# WX0_007_101DL.net
KiCad netlist of a schematic drawn in Altium Designer
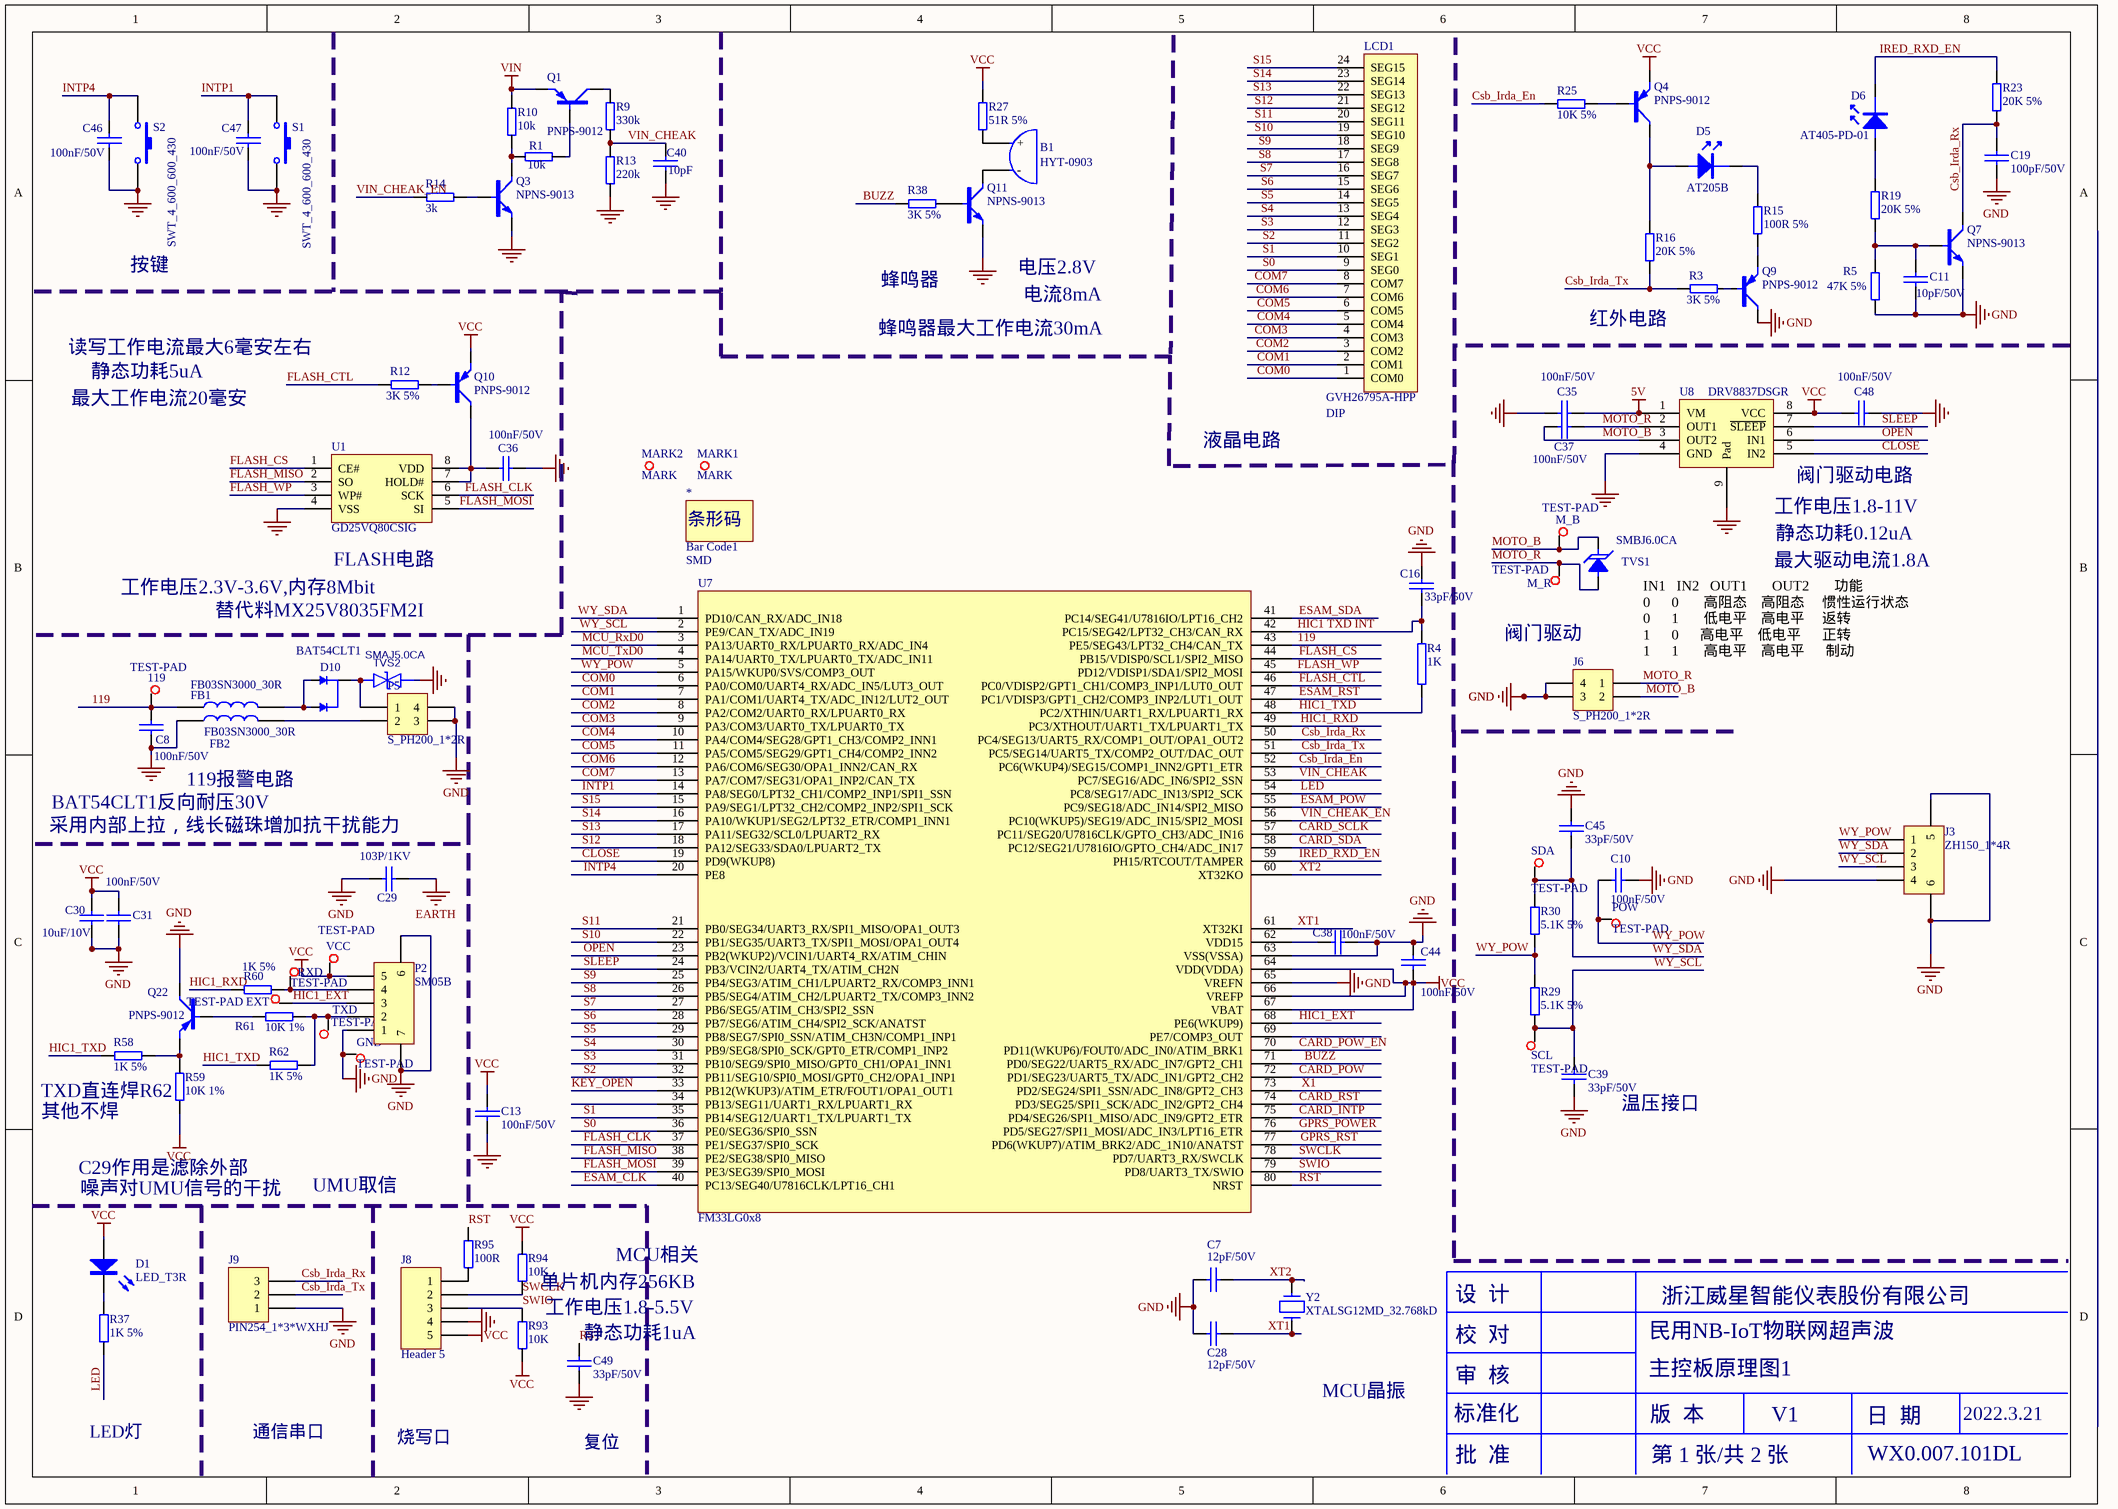
[diagram p0: WX0.007.101DL.SchDoc]

(export (version "E")
  (design (tool "Eeschema 10.0.6"))
  (components
    (comp (ref "*")
      (value "Bar Code1")
      (footprint "Bar Code1")
      (description "条形码 ,填充，无需焊接器件")
      (fields (field (name "PART NUMBER") "AD_WXHJ_Bar Code_02") (field (name "SMD/DIP") "SMD"))
      (libsource (lib "Database_Libs2") (part "05_AD_WXHJ_Bar Code_02"))
    )
    (comp (ref "119")
      (value "TEST-PAD")
      (footprint "TEST-PAD")
      (description "单面焊盘测试点")
      (fields (field (name "PART NUMBER") "AD_WXHJ_TEST-PAD_01"))
      (libsource (lib "Database_Libs2") (part "TEST-PAD"))
    )
    (comp (ref "B1")
      (value "HYT-0903")
      (footprint "HYT-0903")
      (description "直插,直径9mm,高5.5mm,5 V,2 V,30 mA,兴化市华宇电子有限公司,HYT-0903")
      (fields (field (name "PART NUMBER") "1010602-0007"))
      (libsource (lib "Database_Libs2") (part "07_HYT-0903"))
    )
    (comp (ref "C7")
      (value "12pF/50V")
      (footprint "CAP0603")
      (description "12P,50 V,±5%,0603,国巨,CC0603JRNPO9BN12")
      (fields (field (name "PART NUMBER") "101020103-0005"))
      (libsource (lib "Database_Libs2") (part "CC03JPO9_12P"))
    )
    (comp (ref "C8")
      (value "100nF/50V")
      (footprint "CAP0603")
      (description "104pF,50 V,±10%,0603,国巨,CC0603KRX7R9BB104")
      (fields (field (name "PART NUMBER") "101020103-0021"))
      (libsource (lib "Database_Libs2") (part "CC03K7R9_100N"))
    )
    (comp (ref "C10")
      (value "100nF/50V")
      (footprint "CAP0603")
      (description "104pF,50 V,±10%,0603,国巨,CC0603KRX7R9BB104")
      (fields (field (name "PART NUMBER") "101020103-0021"))
      (libsource (lib "Database_Libs2") (part "CC03K7R9_100N"))
    )
    (comp (ref "C11")
      (value "10pF/50V")
      (footprint "CAP0603")
      (description "10pF,50 V,±5%,0603,X7R,国巨,CC0603JRNPO9BN100")
      (fields (field (name "PART NUMBER") "101020103-0014"))
      (libsource (lib "Database_Libs2") (part "CC03JPO9_10P"))
    )
    (comp (ref "C13")
      (value "100nF/50V")
      (footprint "CAP0603")
      (description "104pF,50 V,±10%,0603,国巨,CC0603KRX7R9BB104")
      (fields (field (name "PART NUMBER") "101020103-0021"))
      (libsource (lib "Database_Libs2") (part "CC03K7R9_100N"))
    )
    (comp (ref "C16")
      (value "33pF/50V")
      (footprint "CAP0603")
      (description "33pF,50 V,±10%,0603,国巨,CC0603KRNPO9BN33")
      (fields (field (name "PART NUMBER") "101020103-0027"))
      (libsource (lib "Database_Libs2") (part "CC03KPO9_33P"))
    )
    (comp (ref "C19")
      (value "100pF/50V")
      (footprint "CAP0603")
      (description "101pf,50 V,±5%,0603,国巨,CC0603JRNP09BN101")
      (fields (field (name "PART NUMBER") "101020103-0010"))
      (libsource (lib "Database_Libs2") (part "CC03JPO9_101P"))
    )
    (comp (ref "C28")
      (value "12pF/50V")
      (footprint "CAP0603")
      (description "12P,50 V,±5%,0603,国巨,CC0603JRNPO9BN12")
      (fields (field (name "PART NUMBER") "101020103-0005"))
      (libsource (lib "Database_Libs2") (part "CC03JPO9_12P"))
    )
    (comp (ref "C29")
      (value "103P/1KV")
      (footprint "CAP1206")
      (description "103P/1KV,±10％,1206")
      (fields (field (name "PART NUMBER") "101020101-0003"))
      (libsource (lib "altium-import") (part "root_3_CC03K7R9_100N_"))
    )
    (comp (ref "C30")
      (value "10uF/10V")
      (footprint "CAP0603")
      (description "106pF,10 V,±10%,0603,村田,GRM188R61A106KE47D")
      (fields (field (name "PART NUMBER") "101020103-0026"))
      (libsource (lib "Database_Libs2") (part "CC03K5R6_10U"))
    )
    (comp (ref "C31")
      (value "100nF/50V")
      (footprint "CAP0603")
      (description "104pF,50 V,±10%,0603,国巨,CC0603KRX7R9BB104")
      (fields (field (name "PART NUMBER") "101020103-0021"))
      (libsource (lib "Database_Libs2") (part "CC03K7R9_100N"))
    )
    (comp (ref "C35")
      (value "100nF/50V")
      (footprint "CAP0603")
      (description "104pF,50 V,±10%,0603,国巨,CC0603KRX7R9BB104")
      (fields (field (name "PART NUMBER") "101020103-0021"))
      (libsource (lib "Database_Libs2") (part "CC03K7R9_100N"))
    )
    (comp (ref "C36")
      (value "100nF/50V")
      (footprint "CAP0603")
      (description "104pF,50 V,±10%,0603,国巨,CC0603KRX7R9BB104")
      (fields (field (name "PART NUMBER") "101020103-0021"))
      (libsource (lib "Database_Libs2") (part "CC03K7R9_100N"))
    )
    (comp (ref "C37")
      (value "100nF/50V")
      (footprint "CAP0603")
      (description "104pF,50 V,±10%,0603,国巨,CC0603KRX7R9BB104")
      (fields (field (name "PART NUMBER") "101020103-0021"))
      (libsource (lib "Database_Libs2") (part "CC03K7R9_100N"))
    )
    (comp (ref "C38")
      (value "100nF/50V")
      (footprint "CAP0603")
      (description "104pF,50 V,±10%,0603,国巨,CC0603KRX7R9BB104")
      (fields (field (name "PART NUMBER") "101020103-0021"))
      (libsource (lib "Database_Libs2") (part "CC03K7R9_100N"))
    )
    (comp (ref "C39")
      (value "33pF/50V")
      (footprint "CAP0603")
      (description "33pF,50 V,±10%,0603,国巨,CC0603KRNPO9BN33")
      (fields (field (name "PART NUMBER") "101020103-0027"))
      (libsource (lib "Database_Libs2") (part "CC03KPO9_33P"))
    )
    (comp (ref "C40")
      (value "10pF")
      (footprint "CAP0603")
      (description "无极性电容")
      (libsource (lib "CBB_Lib_SCH") (part "CAP"))
    )
    (comp (ref "C44")
      (value "100nF/50V")
      (footprint "CAP0603")
      (description "104pF,50 V,±10%,0603,国巨,CC0603KRX7R9BB104")
      (fields (field (name "PART NUMBER") "101020103-0021"))
      (libsource (lib "Database_Libs2") (part "CC03K7R9_100N"))
    )
    (comp (ref "C45")
      (value "33pF/50V")
      (footprint "CAP0603")
      (description "33pF,50 V,±10%,0603,国巨,CC0603KRNPO9BN33")
      (fields (field (name "PART NUMBER") "101020103-0027"))
      (libsource (lib "Database_Libs2") (part "CC03KPO9_33P"))
    )
    (comp (ref "C46")
      (value "100nF/50V")
      (footprint "CAP0603")
      (description "104pF,50 V,±10%,0603,国巨,CC0603KRX7R9BB104")
      (fields (field (name "PART NUMBER") "101020103-0021"))
      (libsource (lib "Database_Libs2") (part "CC03K7R9_100N"))
    )
    (comp (ref "C47")
      (value "100nF/50V")
      (footprint "CAP0603")
      (description "104pF,50 V,±10%,0603,国巨,CC0603KRX7R9BB104")
      (fields (field (name "PART NUMBER") "101020103-0021"))
      (libsource (lib "Database_Libs2") (part "CC03K7R9_100N"))
    )
    (comp (ref "C48")
      (value "100nF/50V")
      (footprint "CAP0603")
      (description "104pF,50 V,±10%,0603,国巨,CC0603KRX7R9BB104")
      (fields (field (name "PART NUMBER") "101020103-0021"))
      (libsource (lib "Database_Libs2") (part "CC03K7R9_100N"))
    )
    (comp (ref "C49")
      (value "33pF/50V")
      (footprint "CAP0603")
      (description "33pF,50 V,±10%,0603,国巨,CC0603KRNPO9BN33")
      (fields (field (name "PART NUMBER") "101020103-0027"))
      (libsource (lib "Database_Libs2") (part "CC03KPO9_33P"))
    )
    (comp (ref "D1")
      (value "LED_T3R")
      (footprint "LED2_300")
      (description "圆形插件,3mm 圆形,插件,红光,湖北匡通电子有限公司,3BB4HC")
      (fields (field (name "PART NUMBER") "101040102-0001"))
      (libsource (lib "Database_Libs2") (part "01-LED_T3R"))
    )
    (comp (ref "D5")
      (value "AT205B")
      (footprint "IR_254_1000_500")
      (description "直插,Φ5.8mm圆头透明色，,0.1 A,4 V,5 V,上海品观电子有限公司,AT205B")
      (fields (field (name "PART NUMBER") "101040101-0034"))
      (libsource (lib "Database_Libs2") (part "01_AT205B"))
    )
    (comp (ref "D6")
      (value "AT405-PD-01")
      (footprint "IR_254_1000_500")
      (description "Φ5.8mm圆头黑色，光电接收管,Φ5.8mm,0.01 A,1.2 V,60 V,上海品观电子,AT405-PD-01")
      (fields (field (name "PART NUMBER") "101040101-0035"))
      (libsource (lib "Database_Libs2") (part "01_AT405-PD-01"))
    )
    (comp (ref "D10")
      (value "BAT54CLT1")
      (footprint "SOT-23")
      (description "BAT54CLT1，SOT23-3,SOT23-3,0.2 A,0.8 V,30 V,安森美,BAT54CLT1")
      (fields (field (name "PART NUMBER") "101040101-0038"))
      (libsource (lib "Database_Libs2") (part "02_BAT54CLT1"))
    )
    (comp (ref "EXT")
      (value "TEST-PAD")
      (footprint "TEST-PAD")
      (description "单面焊盘测试点")
      (fields (field (name "PART NUMBER") "AD_WXHJ_TEST-PAD_01"))
      (libsource (lib "Database_Libs2") (part "TEST-PAD"))
    )
    (comp (ref "FB1")
      (value "FB03SN3000_30R")
      (footprint "IND0603")
      (description "chilisin(奇力新),0603,30Ω ±25% @100MHz,150 V,125 ℃,PBY160808T-300Y-N,-55 ℃,不含铅,,,圆盘,30Ω ±25% @100MHz")
      (fields (field (name "PART NUMBER") "109010101-0003"))
      (libsource (lib "Database_Libs2") (part "06_FB03SN3000_30R"))
    )
    (comp (ref "FB2")
      (value "FB03SN3000_30R")
      (footprint "IND0603")
      (description "chilisin(奇力新),0603,30Ω ±25% @100MHz,150 V,125 ℃,PBY160808T-300Y-N,-55 ℃,不含铅,,,圆盘,30Ω ±25% @100MHz")
      (fields (field (name "PART NUMBER") "109010101-0003"))
      (libsource (lib "Database_Libs2") (part "06_FB03SN3000_30R"))
    )
    (comp (ref "GND")
      (value "TEST-PAD")
      (footprint "TEST-PAD")
      (description "单面焊盘测试点")
      (fields (field (name "PART NUMBER") "AD_WXHJ_TEST-PAD_01"))
      (libsource (lib "Database_Libs2") (part "TEST-PAD"))
    )
    (comp (ref "J3")
      (value "ZH150_1*4R")
      (footprint "SMT-1.5-4")
      (description "4针1.5mm间距，贴片卧式,9.0mm*6.5mm,公头,单排,4针1.5mm间距，贴片卧式")
      (fields (field (name "PART NUMBER") "1010902-0126"))
      (libsource (lib "Database_Libs2") (part "ZH150_1*4R"))
    )
    (comp (ref "J6")
      (value "S_PH200_1*2R")
      (footprint "SMT2-2.0")
      (description "PH2.0_2AWR 卧,贴片卧式,母头,单排,2针2.0mm")
      (fields (field (name "PART NUMBER") "1010902-0125"))
      (libsource (lib "") (part "S_PH200_1*2R_1"))
    )
    (comp (ref "J8")
      (value "Header 5")
      (footprint "PIN254_1*5SR")
      (description "Header, 5-Pin")
      (libsource (lib "CBB_Lib_SCH") (part "Header 5"))
    )
    (comp (ref "J9")
      (value "PIN254_1*3*WXHJ")
      (footprint "PIN254_1*3*WXHJ")
      (description "1*3 ，Φ1.0 ，2.54mm，直脚,无需焊接器件")
      (fields (field (name "PART NUMBER") "AD_WXHJ_PinHeader_04"))
      (libsource (lib "Database_Libs2") (part "PIN254_1*3*WXHJ"))
    )
    (comp (ref "LCD1")
      (value "GVH26795A-HPP")
      (footprint "JR-H25808ARP")
      (description "4.4V,61mm*23.5mm*26mm,针脚,段码,126,HTN,半透,60 ℃,-20 ℃,安徽金视界光电科技有限公司,GVH25995A-HPP")
      (fields (field (name "PART NUMBER") "1010801-0050") (field (name "SMD/DIP") "DIP"))
      (libsource (lib "Database_Libs2") (part "03_LCD_GVH25995A-HPP"))
    )
    (comp (ref "MARK1")
      (value "MARK")
      (footprint "MARK")
      (description "MARK点")
      (fields (field (name "PART NUMBER") "AD_WXHJ_MARK_01"))
      (libsource (lib "Database_Libs2") (part "MARK"))
    )
    (comp (ref "MARK2")
      (value "MARK")
      (footprint "MARK")
      (description "MARK点")
      (fields (field (name "PART NUMBER") "AD_WXHJ_MARK_01"))
      (libsource (lib "Database_Libs2") (part "MARK"))
    )
    (comp (ref "M_B")
      (value "TEST-PAD")
      (footprint "TEST-PAD")
      (description "单面焊盘测试点")
      (fields (field (name "PART NUMBER") "AD_WXHJ_TEST-PAD_01"))
      (libsource (lib "Database_Libs2") (part "TEST-PAD"))
    )
    (comp (ref "M_R")
      (value "TEST-PAD")
      (footprint "TEST-PAD")
      (description "单面焊盘测试点")
      (fields (field (name "PART NUMBER") "AD_WXHJ_TEST-PAD_01"))
      (libsource (lib "Database_Libs2") (part "TEST-PAD"))
    )
    (comp (ref "P2") (value "SM05B") (footprint "SMT-1.25-5") (libsource (lib "Connect_WX") (part "SM05B")))
    (comp (ref "P5")
      (value "S_PH200_1*2R")
      (footprint "SMT2-2.0")
      (description "PH2.0_2AWR 卧,贴片卧式,母头,单排,2针2.0mm")
      (fields (field (name "PART NUMBER") "1010902-0125"))
      (libsource (lib "Database_Libs2") (part "S_PH200_1*2R"))
    )
    (comp (ref "POW")
      (value "TEST-PAD")
      (footprint "TEST-PAD")
      (description "单面焊盘测试点")
      (fields (field (name "PART NUMBER") "AD_WXHJ_TEST-PAD_01"))
      (libsource (lib "Database_Libs2") (part "TEST-PAD"))
    )
    (comp (ref "Q1")
      (value "PNPS-9012")
      (footprint "SOT-23")
      (description "9012,PNP,SOT-23,JCET;长电,S9012")
      (fields (field (name "PART NUMBER") "101040201-0001"))
      (libsource (lib "Database_Libs2") (part "03_PNPS-9012"))
    )
    (comp (ref "Q3")
      (value "NPNS-9013")
      (footprint "SOT-23")
      (description "9013,NPN,SOT-23,长电,S9013")
      (fields (field (name "PART NUMBER") "101040201-0002"))
      (libsource (lib "Database_Libs2") (part "03_NPNS-9013"))
    )
    (comp (ref "Q4")
      (value "PNPS-9012")
      (footprint "SOT-23")
      (description "9012,PNP,SOT-23,JCET;长电,S9012")
      (fields (field (name "PART NUMBER") "101040201-0001"))
      (libsource (lib "Database_Libs2") (part "03_PNPS-9012"))
    )
    (comp (ref "Q7")
      (value "NPNS-9013")
      (footprint "SOT-23")
      (description "9013,NPN,SOT-23,长电,S9013")
      (fields (field (name "PART NUMBER") "101040201-0002"))
      (libsource (lib "Database_Libs2") (part "03_NPNS-9013"))
    )
    (comp (ref "Q9")
      (value "PNPS-9012")
      (footprint "SOT-23")
      (description "9012,PNP,SOT-23,JCET;长电,S9012")
      (fields (field (name "PART NUMBER") "101040201-0001"))
      (libsource (lib "Database_Libs2") (part "03_PNPS-9012"))
    )
    (comp (ref "Q10")
      (value "PNPS-9012")
      (footprint "SOT-23")
      (description "9012,PNP,SOT-23,JCET;长电,S9012")
      (fields (field (name "PART NUMBER") "101040201-0001"))
      (libsource (lib "Database_Libs2") (part "03_PNPS-9012"))
    )
    (comp (ref "Q11")
      (value "NPNS-9013")
      (footprint "SOT-23")
      (description "9013,NPN,SOT-23,长电,S9013")
      (fields (field (name "PART NUMBER") "101040201-0002"))
      (libsource (lib "Database_Libs2") (part "03_NPNS-9013"))
    )
    (comp (ref "Q22")
      (value "PNPS-9012")
      (footprint "SOT-23")
      (description "9012,PNP,SOT-23,JCET;长电,S9012")
      (fields (field (name "PART NUMBER") "101040201-0001"))
      (libsource (lib "Database_Libs2") (part "03_PNPS-9012"))
    )
    (comp (ref "R1") (value "10k") (footprint "RES0603") (libsource (lib "CBB_Lib_SCH") (part "RES")))
    (comp (ref "R3")
      (value "3K 5%")
      (footprint "RES0603")
      (description "国巨,±5%,0603,,155 ℃,-55 ℃,RC0603JR-073KL,无铅,100 ppm/℃,1/10W,,3K")
      (fields (field (name "PART NUMBER") "101010103-0006"))
      (libsource (lib "Database_Libs2") (part "RC03J_3K"))
    )
    (comp (ref "R4") (value "1K") (footprint "RES0603") (libsource (lib "PCB_Project1_1") (part "RES2")))
    (comp (ref "R5")
      (value "47K 5%")
      (footprint "RES0603")
      (description "47K,±5%,1/10W,0603,国巨,RC0603JR-0747KL")
      (fields (field (name "PART NUMBER") "101010103-0012"))
      (libsource (lib "Database_Libs2") (part "RC03J_47K"))
    )
    (comp (ref "R9") (value "330k") (footprint "RES0603") (libsource (lib "CBB_Lib_SCH") (part "RES")))
    (comp (ref "R10") (value "10k") (footprint "RES0603") (libsource (lib "CBB_Lib_SCH") (part "RES")))
    (comp (ref "R12")
      (value "3K 5%")
      (footprint "RES0603")
      (description "国巨,±5%,0603,,155 ℃,-55 ℃,RC0603JR-073KL,无铅,100 ppm/℃,1/10W,,3K")
      (fields (field (name "PART NUMBER") "101010103-0006"))
      (libsource (lib "Database_Libs2") (part "RC03J_3K"))
    )
    (comp (ref "R13") (value "220k") (footprint "RES0603") (libsource (lib "CBB_Lib_SCH") (part "RES")))
    (comp (ref "R14") (value "3k") (footprint "RES0603") (libsource (lib "CBB_Lib_SCH") (part "RES")))
    (comp (ref "R15")
      (value "100R 5%")
      (footprint "RES0603")
      (description "100R,±5%,1/10W,0603,国巨,RC0603JR-07100RL")
      (fields (field (name "PART NUMBER") "101010103-0022"))
      (libsource (lib "Database_Libs2") (part "RC03J_100R"))
    )
    (comp (ref "R16")
      (value "20K 5%")
      (footprint "RES0603")
      (description "国巨,±5%,0603,,155 ℃,-55 ℃,RC0603JR-0720KL,无铅,200 ppm/℃,1/10W,,20K")
      (fields (field (name "PART NUMBER") "101010103-0004"))
      (libsource (lib "Database_Libs2") (part "RC03J_20K"))
    )
    (comp (ref "R19")
      (value "20K 5%")
      (footprint "RES0603")
      (description "国巨,±5%,0603,,155 ℃,-55 ℃,RC0603JR-0720KL,无铅,200 ppm/℃,1/10W,,20K")
      (fields (field (name "PART NUMBER") "101010103-0004"))
      (libsource (lib "Database_Libs2") (part "RC03J_20K"))
    )
    (comp (ref "R23")
      (value "20K 5%")
      (footprint "RES0603")
      (description "国巨,±5%,0603,,155 ℃,-55 ℃,RC0603JR-0720KL,无铅,200 ppm/℃,1/10W,,20K")
      (fields (field (name "PART NUMBER") "101010103-0004"))
      (libsource (lib "Database_Libs2") (part "RC03J_20K"))
    )
    (comp (ref "R25")
      (value "10K 5%")
      (footprint "RES0603")
      (description "国巨,±5%,0603,,155 ℃,-55 ℃,RC0603JR-0710KL,无铅,200 ppm/℃,1/10W,,10K")
      (fields (field (name "PART NUMBER") "101010103-0003"))
      (libsource (lib "Database_Libs2") (part "RC03J_10K"))
    )
    (comp (ref "R27")
      (value "51R 5%")
      (footprint "RES0603")
      (description "国巨,±5%,0603,,155 ℃,-55 ℃,RC0603JR-0751RL,无铅,100 ppm/℃,1/10W,,51欧")
      (fields (field (name "PART NUMBER") "101010103-0037"))
      (libsource (lib "Database_Libs2") (part "RC03J_51R"))
    )
    (comp (ref "R29")
      (value "5.1K 5%")
      (footprint "RES0603")
      (description "国巨,±5%,0603,,155 ℃,55 ℃,RC0603JR-075.1KL,无铅,200 ppm/℃,1/10W,,5.1k")
      (fields (field (name "PART NUMBER") "101010103-0015"))
      (libsource (lib "Database_Libs2") (part "RC03J_5.1K"))
    )
    (comp (ref "R30")
      (value "5.1K 5%")
      (footprint "RES0603")
      (description "国巨,±5%,0603,,155 ℃,55 ℃,RC0603JR-075.1KL,无铅,200 ppm/℃,1/10W,,5.1k")
      (fields (field (name "PART NUMBER") "101010103-0015"))
      (libsource (lib "Database_Libs2") (part "RC03J_5.1K"))
    )
    (comp (ref "R37")
      (value "1K 5%")
      (footprint "RES0603")
      (description "1K,±5%,1/10W,0603,国巨,RC0603JR-071KL")
      (fields (field (name "PART NUMBER") "101010103-0008"))
      (libsource (lib "Database_Libs2") (part "RC03J_1K"))
    )
    (comp (ref "R38")
      (value "3K 5%")
      (footprint "RES0603")
      (description "国巨,±5%,0603,,155 ℃,-55 ℃,RC0603JR-073KL,无铅,100 ppm/℃,1/10W,,3K")
      (fields (field (name "PART NUMBER") "101010103-0006"))
      (libsource (lib "Database_Libs2") (part "RC03J_3K"))
    )
    (comp (ref "R58")
      (value "1K 5%")
      (footprint "RES0603")
      (description "1K,±5%,1/10W,0603,国巨,RC0603JR-071KL")
      (fields (field (name "PART NUMBER") "101010103-0008"))
      (libsource (lib "Database_Libs2") (part "RC03J_1K"))
    )
    (comp (ref "R59")
      (value "10K 1%")
      (footprint "RES0603")
      (description "10K±1%,1/10W,0603")
      (fields (field (name "PART NUMBER") "101010103-0052"))
      (libsource (lib "Database_Libs2") (part "RC03J_10K"))
    )
    (comp (ref "R60")
      (value "1K 5%")
      (footprint "RES0603")
      (description "1K,±5%,1/10W,0603,国巨,RC0603JR-071KL")
      (fields (field (name "PART NUMBER") "101010103-0008"))
      (libsource (lib "Database_Libs2") (part "RC03J_1K"))
    )
    (comp (ref "R61")
      (value "10K 1%")
      (footprint "RES0603")
      (description "10K±1%,1/10W,0603")
      (fields (field (name "PART NUMBER") "101010103-0052"))
      (libsource (lib "Database_Libs2") (part "RC03J_10K"))
    )
    (comp (ref "R62")
      (value "1K 5%")
      (footprint "RES0603")
      (description "1K,±5%,1/10W,0603,国巨,RC0603JR-071KL")
      (fields (field (name "PART NUMBER") "101010103-0008"))
      (libsource (lib "Database_Libs2") (part "RC03J_1K"))
    )
    (comp (ref "R93") (value "10K") (footprint "RES0603") (libsource (lib "CBB_Lib_SCH") (part "RES")))
    (comp (ref "R94") (value "10K") (footprint "RES0603") (libsource (lib "CBB_Lib_SCH") (part "RES")))
    (comp (ref "R95") (value "100R") (footprint "RES0603") (libsource (lib "CBB_Lib_SCH") (part "RES")))
    (comp (ref "RXD")
      (value "TEST-PAD")
      (footprint "TEST-PAD")
      (description "单面焊盘测试点")
      (fields (field (name "PART NUMBER") "AD_WXHJ_TEST-PAD_01"))
      (libsource (lib "Database_Libs2") (part "TEST-PAD"))
    )
    (comp (ref "S1")
      (value "SWT_4_600_600_430")
      (footprint "SWT_4_600_600")
      (description "TS-1102,机械轻触,6*6*4.3直插,6*6*4.3直插,乐清市羽欧电子")
      (fields (field (name "PART NUMBER") "1011001-0027"))
      (libsource (lib "Database_Libs2") (part "07_SWT_4_600_600_430"))
    )
    (comp (ref "S2")
      (value "SWT_4_600_600_430")
      (footprint "SWT_4_600_600")
      (description "TS-1102,机械轻触,6*6*4.3直插,6*6*4.3直插,乐清市羽欧电子")
      (fields (field (name "PART NUMBER") "1011001-0027"))
      (libsource (lib "Database_Libs2") (part "07_SWT_4_600_600_430"))
    )
    (comp (ref "SCL")
      (value "TEST-PAD")
      (footprint "TEST-PAD")
      (description "单面焊盘测试点")
      (fields (field (name "PART NUMBER") "AD_WXHJ_TEST-PAD_01"))
      (libsource (lib "Database_Libs2") (part "TEST-PAD"))
    )
    (comp (ref "SDA")
      (value "TEST-PAD")
      (footprint "TEST-PAD")
      (description "单面焊盘测试点")
      (fields (field (name "PART NUMBER") "AD_WXHJ_TEST-PAD_01"))
      (libsource (lib "Database_Libs2") (part "TEST-PAD"))
    )
    (comp (ref "TVS1")
      (value "SMBJ6.0CA")
      (footprint "DO-214AA")
      (description "SMBJ6.0CA,DO-214AA,10.3 V,6.0 V,600 W,58.3 A,800 uA,上海君耀电子有限公司,SMBJ6.0CA")
      (fields (field (name "PART NUMBER") "101040101-0024"))
      (libsource (lib "Database_Libs2") (part "05_SMBJ6.0CA"))
    )
    (comp (ref "TVS2")
      (value "SMAJ5.0CA")
      (footprint "SMAJ5.0CA")
      (fields (field (name "BOM_SUPPLIER PART") "C693487") (field (name "CONTRIBUTOR") "LCSC"))
      (libsource (lib "Discrete_WX") (part "SMAJ5.0CA_C693487"))
    )
    (comp (ref "TXD")
      (value "TEST-PAD")
      (footprint "TEST-PAD")
      (description "单面焊盘测试点")
      (fields (field (name "PART NUMBER") "AD_WXHJ_TEST-PAD_01"))
      (libsource (lib "Database_Libs2") (part "TEST-PAD"))
    )
    (comp (ref "U1")
      (value "GD25VQ80CSIG")
      (footprint "SOP-8L-200MIL")
      (description "GD25VQ80CSIG,SOP8 208mil,北京兆易创新科技股份有限公司,GD25VQ80CSIG")
      (fields (field (name "PART NUMBER") "101050101-0165"))
      (libsource (lib "Database_Libs2") (part "04_GD25VQ80CSIG"))
    )
    (comp (ref "U7") (value "FM33LG0x8") (footprint "LQFP80") (libsource (lib "FM_MCU") (part "FM33LG0x8")))
    (comp (ref "U8")
      (value "DRV8837DSGR")
      (footprint "S-PWSON-N8")
      (description "DRV8837DSGR,S-PWSON-N8,TI,DRV8837DSGR")
      (fields (field (name "PART NUMBER") "101050101-0060"))
      (libsource (lib "Database_Libs2") (part "07_DRV8837DSGR"))
    )
    (comp (ref "VCC")
      (value "TEST-PAD")
      (footprint "TEST-PAD")
      (description "单面焊盘测试点")
      (fields (field (name "PART NUMBER") "AD_WXHJ_TEST-PAD_01"))
      (libsource (lib "Database_Libs2") (part "TEST-PAD"))
    )
    (comp (ref "Y2")
      (value "XTALSG12MD_32.768kD")
      (footprint "SMD-3215_2P")
      (fields (field (name "PART NUMBER") "1010601-0009"))
      (libsource (lib "Database_Libs2") (part "04_XTALSG12MD_32.768kD"))
    )
  )
  (nets
    (net (code "1") (name "/119") (class "Default")
      (node (ref "119") (pin "1") (pinfunction "1_1") (pintype "passive"))
      (node (ref "C8") (pin "1") (pinfunction "1_1") (pintype "passive"))
      (node (ref "FB1") (pin "1") (pinfunction "1_1") (pintype "passive"))
      (node (ref "U7") (pin "43") (pinfunction "PE5/SEG43/LPT32_CH4/CAN_TX_43") (pintype "passive"))
    )
    (net (code "2") (name "/BUZZ") (class "Default")
      (node (ref "R38") (pin "1") (pinfunction "1_1") (pintype "passive"))
      (node (ref "U7") (pin "71") (pinfunction "PD0/SEG22/UART5_RX/ADC_IN7/GPT2_CH1_71") (pintype "passive"))
    )
    (net (code "3") (name "/CARD_INTP") (class "Default")
      (node (ref "U7") (pin "75") (pinfunction "PD4/SEG26/SPI1_MISO/ADC_IN9/GPT2_ETR_75") (pintype "passive"))
    )
    (net (code "4") (name "/CARD_POW") (class "Default")
      (node (ref "U7") (pin "72") (pinfunction "PD1/SEG23/UART5_TX/ADC_IN1/GPT2_CH2_72") (pintype "passive"))
    )
    (net (code "5") (name "/CARD_POW_EN") (class "Default")
      (node (ref "U7") (pin "70") (pinfunction "PD11(WKUP6)/FOUT0/ADC_IN0/ATIM_BRK1_70") (pintype "passive"))
    )
    (net (code "6") (name "/CARD_RST") (class "Default")
      (node (ref "U7") (pin "74") (pinfunction "PD3/SEG25/SPI1_SCK/ADC_IN2/GPT2_CH4_74") (pintype "passive"))
    )
    (net (code "7") (name "/CARD_SCLK") (class "Default")
      (node (ref "U7") (pin "57") (pinfunction "PC11/SEG20/U7816CLK/GPTO_CH3/ADC_IN16_57") (pintype "passive"))
    )
    (net (code "8") (name "/CARD_SDA") (class "Default")
      (node (ref "U7") (pin "58") (pinfunction "PC12/SEG21/U7816IO/GPTO_CH4/ADC_IN17_58") (pintype "passive"))
    )
    (net (code "9") (name "/CLOSE") (class "Default")
      (node (ref "U7") (pin "19") (pinfunction "PD9(WKUP8)_19") (pintype "passive"))
      (node (ref "U8") (pin "5") (pinfunction "IN2_5") (pintype "passive"))
    )
    (net (code "10") (name "/COM0") (class "Default")
      (node (ref "LCD1") (pin "1") (pinfunction "COM0_1") (pintype "passive"))
      (node (ref "U7") (pin "6") (pinfunction "PA0/COM0/UART4_RX/ADC_IN5/LUT3_OUT_6") (pintype "passive"))
    )
    (net (code "11") (name "/COM1") (class "Default")
      (node (ref "LCD1") (pin "2") (pinfunction "COM1_2") (pintype "passive"))
      (node (ref "U7") (pin "7") (pinfunction "PA1/COM1/UART4_TX/ADC_IN12/LUT2_OUT_7") (pintype "passive"))
    )
    (net (code "12") (name "/COM2") (class "Default")
      (node (ref "LCD1") (pin "3") (pinfunction "COM2_3") (pintype "passive"))
      (node (ref "U7") (pin "8") (pinfunction "PA2/COM2/UART0_RX/LPUART0_RX_8") (pintype "passive"))
    )
    (net (code "13") (name "/COM3") (class "Default")
      (node (ref "LCD1") (pin "4") (pinfunction "COM3_4") (pintype "passive"))
      (node (ref "U7") (pin "9") (pinfunction "PA3/COM3/UART0_TX/LPUART0_TX_9") (pintype "passive"))
    )
    (net (code "14") (name "/COM4") (class "Default")
      (node (ref "LCD1") (pin "5") (pinfunction "COM4_5") (pintype "passive"))
      (node (ref "U7") (pin "10") (pinfunction "PA4/COM4/SEG28/GPT1_CH3/COMP2_INN1_10") (pintype "passive"))
    )
    (net (code "15") (name "/COM5") (class "Default")
      (node (ref "LCD1") (pin "6") (pinfunction "COM5_6") (pintype "passive"))
      (node (ref "U7") (pin "11") (pinfunction "PA5/COM5/SEG29/GPT1_CH4/COMP2_INN2_11") (pintype "passive"))
    )
    (net (code "16") (name "/COM6") (class "Default")
      (node (ref "LCD1") (pin "7") (pinfunction "COM6_7") (pintype "passive"))
      (node (ref "U7") (pin "12") (pinfunction "PA6/COM6/SEG30/OPA1_INN2/CAN_RX_12") (pintype "passive"))
    )
    (net (code "17") (name "/COM7") (class "Default")
      (node (ref "LCD1") (pin "8") (pinfunction "COM7_8") (pintype "passive"))
      (node (ref "U7") (pin "13") (pinfunction "PA7/COM7/SEG31/OPA1_INP2/CAN_TX_13") (pintype "passive"))
    )
    (net (code "18") (name "/Csb_Irda_En") (class "Default")
      (node (ref "R25") (pin "2") (pinfunction "2_2") (pintype "passive"))
      (node (ref "U7") (pin "52") (pinfunction "PC6(WKUP4)/SEG15/COMP1_INN2/GPT1_ETR_52") (pintype "passive"))
    )
    (net (code "19") (name "/Csb_Irda_Rx") (class "Default")
      (node (ref "C19") (pin "1") (pinfunction "1_1") (pintype "passive"))
      (node (ref "J9") (pin "3") (pinfunction "3_3") (pintype "passive"))
      (node (ref "Q7") (pin "3") (pinfunction "C_3") (pintype "passive"))
      (node (ref "R23") (pin "1") (pinfunction "1_1") (pintype "passive"))
      (node (ref "U7") (pin "50") (pinfunction "PC4/SEG13/UART5_RX/COMP1_OUT/OPA1_OUT2_50") (pintype "passive"))
    )
    (net (code "20") (name "/Csb_Irda_Tx") (class "Default")
      (node (ref "J9") (pin "2") (pinfunction "2_2") (pintype "passive"))
      (node (ref "R16") (pin "1") (pinfunction "1_1") (pintype "passive"))
      (node (ref "R3") (pin "1") (pinfunction "1_1") (pintype "passive"))
      (node (ref "U7") (pin "51") (pinfunction "PC5/SEG14/UART5_TX/COMP2_OUT/DAC_OUT_51") (pintype "passive"))
    )
    (net (code "21") (name "/ESAM_CLK") (class "Default")
      (node (ref "U7") (pin "40") (pinfunction "PC13/SEG40/U7816CLK/LPT16_CH1_40") (pintype "passive"))
    )
    (net (code "22") (name "/ESAM_POW") (class "Default")
      (node (ref "U7") (pin "55") (pinfunction "PC9/SEG18/ADC_IN14/SPI2_MISO_55") (pintype "passive"))
    )
    (net (code "23") (name "/ESAM_RST") (class "Default")
      (node (ref "U7") (pin "47") (pinfunction "PC1/VDISP3/GPT1_CH2/COMP3_INP2/LUT1_OUT_47") (pintype "passive"))
    )
    (net (code "24") (name "/ESAM_SDA") (class "Default")
      (node (ref "U7") (pin "41") (pinfunction "PC14/SEG41/U7816IO/LPT16_CH2_41") (pintype "passive"))
    )
    (net (code "25") (name "/FLASH_CLK") (class "Default")
      (node (ref "U1") (pin "6") (pinfunction "SCK_6") (pintype "passive"))
      (node (ref "U7") (pin "37") (pinfunction "PE1/SEG37/SPI0_SCK_37") (pintype "passive"))
    )
    (net (code "26") (name "/FLASH_CS") (class "Default")
      (node (ref "U1") (pin "1") (pinfunction "CE#_1") (pintype "passive"))
      (node (ref "U7") (pin "44") (pinfunction "PB15/VDISP0/SCL1/SPI2_MISO_44") (pintype "passive"))
    )
    (net (code "27") (name "/FLASH_CTL") (class "Default")
      (node (ref "R12") (pin "1") (pinfunction "1_1") (pintype "passive"))
      (node (ref "U7") (pin "46") (pinfunction "PC0/VDISP2/GPT1_CH1/COMP3_INP1/LUT0_OUT_46") (pintype "passive"))
    )
    (net (code "28") (name "/FLASH_MISO") (class "Default")
      (node (ref "U1") (pin "2") (pinfunction "SO_2") (pintype "passive"))
      (node (ref "U7") (pin "38") (pinfunction "PE2/SEG38/SPI0_MISO_38") (pintype "passive"))
    )
    (net (code "29") (name "/FLASH_MOSI") (class "Default")
      (node (ref "U1") (pin "5") (pinfunction "SI_5") (pintype "passive"))
      (node (ref "U7") (pin "39") (pinfunction "PE3/SEG39/SPI0_MOSI_39") (pintype "passive"))
    )
    (net (code "30") (name "/FLASH_WP") (class "Default")
      (node (ref "U1") (pin "3") (pinfunction "WP#_3") (pintype "passive"))
      (node (ref "U7") (pin "45") (pinfunction "PD12/VDISP1/SDA1/SPI2_MOSI_45") (pintype "passive"))
    )
    (net (code "31") (name "/GPRS_POWER") (class "Default")
      (node (ref "U7") (pin "76") (pinfunction "PD5/SEG27/SPI1_MOSI/ADC_IN3/LPT16_ETR_76") (pintype "passive"))
    )
    (net (code "32") (name "/GPRS_RST") (class "Default")
      (node (ref "U7") (pin "77") (pinfunction "PD6(WKUP7)/ATIM_BRK2/ADC_1N10/ANATST_77") (pintype "passive"))
    )
    (net (code "33") (name "/HIC1 TXD INT") (class "Default")
      (node (ref "C16") (pin "1") (pinfunction "1_1") (pintype "passive"))
      (node (ref "R4") (pin "2") (pinfunction "2_2") (pintype "passive"))
      (node (ref "U7") (pin "42") (pinfunction "PC15/SEG42/LPT32_CH3/CAN_RX_42") (pintype "passive"))
    )
    (net (code "34") (name "/HIC1_EXT") (class "Default")
      (node (ref "EXT") (pin "1") (pinfunction "1_1") (pintype "passive"))
      (node (ref "P2") (pin "3") (pinfunction "3_3") (pintype "passive"))
      (node (ref "U7") (pin "68") (pinfunction "PE6(WKUP9)_68") (pintype "passive"))
    )
    (net (code "35") (name "/HIC1_RXD") (class "Default")
      (node (ref "R60") (pin "1") (pinfunction "1_1") (pintype "passive"))
      (node (ref "U7") (pin "49") (pinfunction "PC3/XTHOUT/UART1_TX/LPUART1_TX_49") (pintype "passive"))
    )
    (net (code "36") (name "/HIC1_TXD") (class "Default")
      (node (ref "R4") (pin "1") (pinfunction "1_1") (pintype "passive"))
      (node (ref "R58") (pin "1") (pinfunction "1_1") (pintype "passive"))
      (node (ref "R62") (pin "1") (pinfunction "1_1") (pintype "passive"))
      (node (ref "U7") (pin "48") (pinfunction "PC2/XTHIN/UART1_RX/LPUART1_RX_48") (pintype "passive"))
    )
    (net (code "37") (name "/INTP1") (class "Default")
      (node (ref "C47") (pin "2") (pinfunction "2_2") (pintype "passive"))
      (node (ref "S1") (pin "1") (pinfunction "1_1") (pintype "passive"))
      (node (ref "U7") (pin "14") (pinfunction "PA8/SEG0/LPT32_CH1/COMP2_INP1/SPI1_SSN_14") (pintype "passive"))
    )
    (net (code "38") (name "/INTP4") (class "Default")
      (node (ref "C46") (pin "2") (pinfunction "2_2") (pintype "passive"))
      (node (ref "S2") (pin "1") (pinfunction "1_1") (pintype "passive"))
      (node (ref "U7") (pin "20") (pinfunction "PE8_20") (pintype "passive"))
    )
    (net (code "39") (name "/IRED_RXD_EN") (class "Default")
      (node (ref "D6") (pin "2") (pinfunction "2_2") (pintype "passive"))
      (node (ref "R23") (pin "2") (pinfunction "2_2") (pintype "passive"))
      (node (ref "U7") (pin "59") (pinfunction "PH15/RTCOUT/TAMPER_59") (pintype "passive"))
    )
    (net (code "40") (name "/KEY_OPEN") (class "Default")
      (node (ref "U7") (pin "33") (pinfunction "PB12(WKUP3)/ATIM_ETR/FOUT1/OPA1_OUT1_33") (pintype "passive"))
    )
    (net (code "41") (name "/LED") (class "Default")
      (node (ref "R37") (pin "1") (pinfunction "1_1") (pintype "passive"))
      (node (ref "U7") (pin "54") (pinfunction "PC8/SEG17/ADC_IN13/SPI2_SCK_54") (pintype "passive"))
    )
    (net (code "42") (name "/MCU_RxD0") (class "Default")
      (node (ref "U7") (pin "3") (pinfunction "PA13/UART0_RX/LPUART0_RX/ADC_IN4_3") (pintype "passive"))
    )
    (net (code "43") (name "/MCU_TxD0") (class "Default")
      (node (ref "U7") (pin "4") (pinfunction "PA14/UART0_TX/LPUART0_TX/ADC_IN11_4") (pintype "passive"))
    )
    (net (code "44") (name "/MOTO_B") (class "Default")
      (node (ref "C37") (pin "2") (pinfunction "2_2") (pintype "passive"))
      (node (ref "J6") (pin "2") (pinfunction "2_2") (pintype "passive"))
      (node (ref "M_B") (pin "1") (pinfunction "1_1") (pintype "passive"))
      (node (ref "TVS1") (pin "2") (pinfunction "2_2") (pintype "passive"))
      (node (ref "U8") (pin "3") (pinfunction "OUT2_3") (pintype "passive"))
    )
    (net (code "45") (name "/MOTO_R") (class "Default")
      (node (ref "C37") (pin "1") (pinfunction "1_1") (pintype "passive"))
      (node (ref "J6") (pin "1") (pinfunction "1_1") (pintype "passive"))
      (node (ref "M_R") (pin "1") (pinfunction "1_1") (pintype "passive"))
      (node (ref "TVS1") (pin "1") (pinfunction "1_1") (pintype "passive"))
      (node (ref "U8") (pin "2") (pinfunction "OUT1_2") (pintype "passive"))
    )
    (net (code "46") (name "/OPEN") (class "Default")
      (node (ref "U7") (pin "23") (pinfunction "PB2(WKUP2)/VCIN1/UART4_RX/ATIM_CHIN_23") (pintype "passive"))
      (node (ref "U8") (pin "6") (pinfunction "IN1_6") (pintype "passive"))
    )
    (net (code "47") (name "/RST") (class "Default")
      (node (ref "C49") (pin "2") (pinfunction "2_2") (pintype "passive"))
      (node (ref "R95") (pin "1") (pintype "passive"))
      (node (ref "U7") (pin "80") (pinfunction "NRST_80") (pintype "passive"))
    )
    (net (code "48") (name "/S0") (class "Default")
      (node (ref "LCD1") (pin "9") (pinfunction "SEG0_9") (pintype "passive"))
      (node (ref "U7") (pin "36") (pinfunction "PE0/SEG36/SPI0_SSN_36") (pintype "passive"))
    )
    (net (code "49") (name "/S1") (class "Default")
      (node (ref "LCD1") (pin "10") (pinfunction "SEG1_10") (pintype "passive"))
      (node (ref "U7") (pin "35") (pinfunction "PB14/SEG12/UART1_TX/LPUART1_TX_35") (pintype "passive"))
    )
    (net (code "50") (name "/S2") (class "Default")
      (node (ref "LCD1") (pin "11") (pinfunction "SEG2_11") (pintype "passive"))
      (node (ref "U7") (pin "32") (pinfunction "PB11/SEG10/SPI0_MOSI/GPT0_CH2/OPA1_INP1_32") (pintype "passive"))
    )
    (net (code "51") (name "/S3") (class "Default")
      (node (ref "LCD1") (pin "12") (pinfunction "SEG3_12") (pintype "passive"))
      (node (ref "U7") (pin "31") (pinfunction "PB10/SEG9/SPI0_MISO/GPT0_CH1/OPA1_INN1_31") (pintype "passive"))
    )
    (net (code "52") (name "/S4") (class "Default")
      (node (ref "LCD1") (pin "13") (pinfunction "SEG4_13") (pintype "passive"))
      (node (ref "U7") (pin "30") (pinfunction "PB9/SEG8/SPI0_SCK/GPT0_ETR/COMP1_INP2_30") (pintype "passive"))
    )
    (net (code "53") (name "/S5") (class "Default")
      (node (ref "LCD1") (pin "14") (pinfunction "SEG5_14") (pintype "passive"))
      (node (ref "U7") (pin "29") (pinfunction "PB8/SEG7/SPI0_SSN/ATIM_CH3N/COMP1_INP1_29") (pintype "passive"))
    )
    (net (code "54") (name "/S6") (class "Default")
      (node (ref "LCD1") (pin "15") (pinfunction "SEG6_15") (pintype "passive"))
      (node (ref "U7") (pin "28") (pinfunction "PB7/SEG6/ATIM_CH4/SPI2_SCK/ANATST_28") (pintype "passive"))
    )
    (net (code "55") (name "/S7") (class "Default")
      (node (ref "LCD1") (pin "16") (pinfunction "SEG7_16") (pintype "passive"))
      (node (ref "U7") (pin "27") (pinfunction "PB6/SEG5/ATIM_CH3/SPI2_SSN_27") (pintype "passive"))
    )
    (net (code "56") (name "/S8") (class "Default")
      (node (ref "LCD1") (pin "17") (pinfunction "SEG8_17") (pintype "passive"))
      (node (ref "U7") (pin "26") (pinfunction "PB5/SEG4/ATIM_CH2/LPUART2_TX/COMP3_INN2_26") (pintype "passive"))
    )
    (net (code "57") (name "/S9") (class "Default")
      (node (ref "LCD1") (pin "18") (pinfunction "SEG9_18") (pintype "passive"))
      (node (ref "U7") (pin "25") (pinfunction "PB4/SEG3/ATIM_CH1/LPUART2_RX/COMP3_INN1_25") (pintype "passive"))
    )
    (net (code "58") (name "/S10") (class "Default")
      (node (ref "LCD1") (pin "19") (pinfunction "SEG10_19") (pintype "passive"))
      (node (ref "U7") (pin "22") (pinfunction "PB1/SEG35/UART3_TX/SPI1_MOSI/OPA1_OUT4_22") (pintype "passive"))
    )
    (net (code "59") (name "/S11") (class "Default")
      (node (ref "LCD1") (pin "20") (pinfunction "SEG11_20") (pintype "passive"))
      (node (ref "U7") (pin "21") (pinfunction "PB0/SEG34/UART3_RX/SPI1_MISO/OPA1_OUT3_21") (pintype "passive"))
    )
    (net (code "60") (name "/S12") (class "Default")
      (node (ref "LCD1") (pin "21") (pinfunction "SEG12_21") (pintype "passive"))
      (node (ref "U7") (pin "18") (pinfunction "PA12/SEG33/SDA0/LPUART2_TX_18") (pintype "passive"))
    )
    (net (code "61") (name "/S13") (class "Default")
      (node (ref "LCD1") (pin "22") (pinfunction "SEG13_22") (pintype "passive"))
      (node (ref "U7") (pin "17") (pinfunction "PA11/SEG32/SCL0/LPUART2_RX_17") (pintype "passive"))
    )
    (net (code "62") (name "/S14") (class "Default")
      (node (ref "LCD1") (pin "23") (pinfunction "SEG14_23") (pintype "passive"))
      (node (ref "U7") (pin "16") (pinfunction "PA10/WKUP1/SEG2/LPT32_ETR/COMP1_INN1_16") (pintype "passive"))
    )
    (net (code "63") (name "/S15") (class "Default")
      (node (ref "LCD1") (pin "24") (pinfunction "SEG15_24") (pintype "passive"))
      (node (ref "U7") (pin "15") (pinfunction "PA9/SEG1/LPT32_CH2/COMP2_INP2/SPI1_SCK_15") (pintype "passive"))
    )
    (net (code "64") (name "/SLEEP") (class "Default")
      (node (ref "U7") (pin "24") (pinfunction "PB3/VCIN2/UART4_TX/ATIM_CH2N_24") (pintype "passive"))
      (node (ref "U8") (pin "7") (pinfunction "~{SLEEP}_7") (pintype "passive"))
    )
    (net (code "65") (name "/SWCLK") (class "Default")
      (node (ref "J8") (pin "2") (pinfunction "2_2") (pintype "passive"))
      (node (ref "R94") (pin "1") (pintype "passive"))
      (node (ref "U7") (pin "78") (pinfunction "PD7/UART3_RX/SWCLK_78") (pintype "passive"))
    )
    (net (code "66") (name "/SWIO") (class "Default")
      (node (ref "J8") (pin "3") (pinfunction "3_3") (pintype "passive"))
      (node (ref "R93") (pin "2") (pintype "passive"))
      (node (ref "U7") (pin "79") (pinfunction "PD8/UART3_TX/SWIO_79") (pintype "passive"))
    )
    (net (code "67") (name "/VIN_CHEAK") (class "Default")
      (node (ref "C40") (pin "2") (pintype "passive"))
      (node (ref "R13") (pin "1") (pintype "passive"))
      (node (ref "R9") (pin "2") (pintype "passive"))
      (node (ref "U7") (pin "53") (pinfunction "PC7/SEG16/ADC_IN6/SPI2_SSN_53") (pintype "passive"))
    )
    (net (code "68") (name "/VIN_CHEAK_EN") (class "Default")
      (node (ref "R14") (pin "1") (pintype "passive"))
      (node (ref "U7") (pin "56") (pinfunction "PC10(WKUP5)/SEG19/ADC_IN15/SPI2_MOSI_56") (pintype "passive"))
    )
    (net (code "69") (name "/WY_POW") (class "Default")
      (node (ref "C10") (pin "1") (pinfunction "1_1") (pintype "passive"))
      (node (ref "J3") (pin "1") (pinfunction "1_1") (pintype "passive"))
      (node (ref "POW") (pin "1") (pinfunction "1_1") (pintype "passive"))
      (node (ref "R29") (pin "1") (pinfunction "1_1") (pintype "passive"))
      (node (ref "R30") (pin "1") (pinfunction "1_1") (pintype "passive"))
      (node (ref "U7") (pin "5") (pinfunction "PA15/WKUP0/SVS/COMP3_OUT_5") (pintype "passive"))
    )
    (net (code "70") (name "/WY_SCL") (class "Default")
      (node (ref "C39") (pin "2") (pinfunction "2_2") (pintype "passive"))
      (node (ref "J3") (pin "3") (pinfunction "3_3") (pintype "passive"))
      (node (ref "R29") (pin "2") (pinfunction "2_2") (pintype "passive"))
      (node (ref "SCL") (pin "1") (pinfunction "1_1") (pintype "passive"))
      (node (ref "U7") (pin "2") (pinfunction "PE9/CAN_TX/ADC_IN19_2") (pintype "passive"))
    )
    (net (code "71") (name "/WY_SDA") (class "Default")
      (node (ref "C45") (pin "1") (pinfunction "1_1") (pintype "passive"))
      (node (ref "J3") (pin "2") (pinfunction "2_2") (pintype "passive"))
      (node (ref "R30") (pin "2") (pinfunction "2_2") (pintype "passive"))
      (node (ref "SDA") (pin "1") (pinfunction "1_1") (pintype "passive"))
      (node (ref "U7") (pin "1") (pinfunction "PD10/CAN_RX/ADC_IN18_1") (pintype "passive"))
    )
    (net (code "72") (name "/X1") (class "Default")
      (node (ref "U7") (pin "73") (pinfunction "PD2/SEG24/SPI1_SSN/ADC_IN8/GPT2_CH3_73") (pintype "passive"))
    )
    (net (code "73") (name "/XT1") (class "Default")
      (node (ref "C28") (pin "2") (pinfunction "2_2") (pintype "passive"))
      (node (ref "U7") (pin "61") (pinfunction "XT32KI_61") (pintype "passive"))
      (node (ref "Y2") (pin "1") (pinfunction "1_1") (pintype "passive"))
    )
    (net (code "74") (name "/XT2") (class "Default")
      (node (ref "C7") (pin "2") (pinfunction "2_2") (pintype "passive"))
      (node (ref "U7") (pin "60") (pinfunction "XT32KO_60") (pintype "passive"))
      (node (ref "Y2") (pin "2") (pinfunction "2_2") (pintype "passive"))
    )
    (net (code "75") (name "5V") (class "Default")
      (node (ref "C35") (pin "1") (pinfunction "1_1") (pintype "passive"))
      (node (ref "U8") (pin "1") (pinfunction "VM_1") (pintype "passive"))
    )
    (net (code "76") (name "EARTH") (class "Default")
      (node (ref "C29") (pin "1") (pinfunction "1_1") (pintype "passive"))
    )
    (net (code "77") (name "GND") (class "Default")
      (node (ref "C10") (pin "2") (pinfunction "2_2") (pintype "passive"))
      (node (ref "C11") (pin "2") (pinfunction "2_2") (pintype "passive"))
      (node (ref "C13") (pin "1") (pinfunction "1_1") (pintype "passive"))
      (node (ref "C16") (pin "2") (pinfunction "2_2") (pintype "passive"))
      (node (ref "C19") (pin "2") (pinfunction "2_2") (pintype "passive"))
      (node (ref "C28") (pin "1") (pinfunction "1_1") (pintype "passive"))
      (node (ref "C29") (pin "2") (pinfunction "2_2") (pintype "passive"))
      (node (ref "C30") (pin "2") (pinfunction "2_2") (pintype "passive"))
      (node (ref "C31") (pin "2") (pinfunction "2_2") (pintype "passive"))
      (node (ref "C35") (pin "2") (pinfunction "2_2") (pintype "passive"))
      (node (ref "C36") (pin "2") (pinfunction "2_2") (pintype "passive"))
      (node (ref "C38") (pin "2") (pinfunction "2_2") (pintype "passive"))
      (node (ref "C39") (pin "1") (pinfunction "1_1") (pintype "passive"))
      (node (ref "C40") (pin "1") (pintype "passive"))
      (node (ref "C44") (pin "1") (pinfunction "1_1") (pintype "passive"))
      (node (ref "C45") (pin "2") (pinfunction "2_2") (pintype "passive"))
      (node (ref "C46") (pin "1") (pinfunction "1_1") (pintype "passive"))
      (node (ref "C47") (pin "1") (pinfunction "1_1") (pintype "passive"))
      (node (ref "C48") (pin "1") (pinfunction "1_1") (pintype "passive"))
      (node (ref "C49") (pin "1") (pinfunction "1_1") (pintype "passive"))
      (node (ref "C7") (pin "1") (pinfunction "1_1") (pintype "passive"))
      (node (ref "C8") (pin "2") (pinfunction "2_2") (pintype "passive"))
      (node (ref "FB2") (pin "1") (pinfunction "1_1") (pintype "passive"))
      (node (ref "GND") (pin "1") (pinfunction "1_1") (pintype "passive"))
      (node (ref "J3") (pin "4") (pinfunction "4_4") (pintype "passive"))
      (node (ref "J3") (pin "5") (pinfunction "5_5") (pintype "passive"))
      (node (ref "J3") (pin "6") (pinfunction "6_6") (pintype "passive"))
      (node (ref "J6") (pin "3") (pinfunction "3_3") (pintype "passive"))
      (node (ref "J6") (pin "4") (pinfunction "4_4") (pintype "passive"))
      (node (ref "J8") (pin "4") (pinfunction "4_4") (pintype "passive"))
      (node (ref "J9") (pin "1") (pinfunction "1_1") (pintype "passive"))
      (node (ref "P2") (pin "1") (pinfunction "1_1") (pintype "passive"))
      (node (ref "P2") (pin "6") (pinfunction "6_6") (pintype "passive"))
      (node (ref "P2") (pin "7") (pinfunction "7_7") (pintype "passive"))
      (node (ref "P5") (pin "3") (pinfunction "3_3") (pintype "passive"))
      (node (ref "P5") (pin "4") (pinfunction "4_4") (pintype "passive"))
      (node (ref "Q11") (pin "2") (pinfunction "E_2") (pintype "passive"))
      (node (ref "Q22") (pin "3") (pinfunction "C_3") (pintype "passive"))
      (node (ref "Q3") (pin "2") (pinfunction "E_2") (pintype "passive"))
      (node (ref "Q7") (pin "2") (pinfunction "E_2") (pintype "passive"))
      (node (ref "Q9") (pin "3") (pinfunction "C_3") (pintype "passive"))
      (node (ref "R13") (pin "2") (pintype "passive"))
      (node (ref "R5") (pin "1") (pinfunction "1_1") (pintype "passive"))
      (node (ref "S1") (pin "2") (pinfunction "2_2") (pintype "passive"))
      (node (ref "S2") (pin "2") (pinfunction "2_2") (pintype "passive"))
      (node (ref "TVS2") (pin "2") (pinfunction "2_2") (pintype "passive"))
      (node (ref "U1") (pin "4") (pinfunction "VSS_4") (pintype "passive"))
      (node (ref "U7") (pin "63") (pinfunction "VSS(VSSA)_63") (pintype "passive"))
      (node (ref "U7") (pin "65") (pinfunction "VREFN_65") (pintype "passive"))
      (node (ref "U8") (pin "4") (pinfunction "GND_4") (pintype "passive"))
      (node (ref "U8") (pin "9") (pinfunction "Pad_9") (pintype "passive"))
    )
    (net (code "78") (name "Net-(B1-+)") (class "Default")
      (node (ref "B1") (pin "1") (pinfunction "+_1") (pintype "passive"))
      (node (ref "R27") (pin "1") (pinfunction "1_1") (pintype "passive"))
    )
    (net (code "79") (name "Net-(B1--)") (class "Default")
      (node (ref "B1") (pin "2") (pinfunction "-_2") (pintype "passive"))
      (node (ref "Q11") (pin "3") (pinfunction "C_3") (pintype "passive"))
    )
    (net (code "80") (name "Net-(D1-Pad2)") (class "Default")
      (node (ref "D1") (pin "2") (pinfunction "2_2") (pintype "passive"))
      (node (ref "R37") (pin "2") (pinfunction "2_2") (pintype "passive"))
    )
    (net (code "81") (name "Net-(D5-Pad2)") (class "Default")
      (node (ref "D5") (pin "2") (pinfunction "2_2") (pintype "passive"))
      (node (ref "R15") (pin "2") (pinfunction "2_2") (pintype "passive"))
    )
    (net (code "82") (name "Net-(D6-Pad1)") (class "Default")
      (node (ref "D6") (pin "1") (pinfunction "1_1") (pintype "passive"))
      (node (ref "R19") (pin "2") (pinfunction "2_2") (pintype "passive"))
    )
    (net (code "83") (name "Net-(D10-A-Pad1)") (class "Default")
      (node (ref "D10") (pin "1") (pinfunction "A_1") (pintype "passive"))
      (node (ref "D10") (pin "2") (pinfunction "A_2") (pintype "passive"))
      (node (ref "FB1") (pin "2") (pinfunction "2_2") (pintype "passive"))
    )
    (net (code "84") (name "Net-(D10-C)") (class "Default")
      (node (ref "D10") (pin "3") (pinfunction "C_3") (pintype "passive"))
      (node (ref "P5") (pin "1") (pinfunction "1_1") (pintype "passive"))
      (node (ref "TVS2") (pin "1") (pinfunction "1_1") (pintype "passive"))
    )
    (net (code "85") (name "Net-(FB2-Pad2)") (class "Default")
      (node (ref "FB2") (pin "2") (pinfunction "2_2") (pintype "passive"))
      (node (ref "P5") (pin "2") (pinfunction "2_2") (pintype "passive"))
    )
    (net (code "86") (name "Net-(J8-Pad1)") (class "Default")
      (node (ref "J8") (pin "1") (pinfunction "1_1") (pintype "passive"))
      (node (ref "R95") (pin "2") (pintype "passive"))
    )
    (net (code "87") (name "Net-(P2-Pad2)") (class "Default")
      (node (ref "P2") (pin "2") (pinfunction "2_2") (pintype "passive"))
      (node (ref "R61") (pin "2") (pinfunction "2_2") (pintype "passive"))
      (node (ref "R62") (pin "2") (pinfunction "2_2") (pintype "passive"))
      (node (ref "TXD") (pin "1") (pinfunction "1_1") (pintype "passive"))
    )
    (net (code "88") (name "Net-(P2-Pad4)") (class "Default")
      (node (ref "P2") (pin "4") (pinfunction "4_4") (pintype "passive"))
      (node (ref "R60") (pin "2") (pinfunction "2_2") (pintype "passive"))
      (node (ref "RXD") (pin "1") (pinfunction "1_1") (pintype "passive"))
    )
    (net (code "89") (name "Net-(Q1-B)") (class "Default")
      (node (ref "Q1") (pin "1") (pinfunction "B_1") (pintype "passive"))
      (node (ref "R1") (pin "2") (pintype "passive"))
    )
    (net (code "90") (name "Net-(Q1-C)") (class "Default")
      (node (ref "Q1") (pin "3") (pinfunction "C_3") (pintype "passive"))
      (node (ref "R9") (pin "1") (pintype "passive"))
    )
    (net (code "91") (name "Net-(Q3-B)") (class "Default")
      (node (ref "Q3") (pin "1") (pinfunction "B_1") (pintype "passive"))
      (node (ref "R14") (pin "2") (pintype "passive"))
    )
    (net (code "92") (name "Net-(Q3-C)") (class "Default")
      (node (ref "Q3") (pin "3") (pinfunction "C_3") (pintype "passive"))
      (node (ref "R1") (pin "1") (pintype "passive"))
      (node (ref "R10") (pin "1") (pintype "passive"))
    )
    (net (code "93") (name "Net-(Q4-B)") (class "Default")
      (node (ref "Q4") (pin "1") (pinfunction "B_1") (pintype "passive"))
      (node (ref "R25") (pin "1") (pinfunction "1_1") (pintype "passive"))
    )
    (net (code "94") (name "Net-(Q4-C)") (class "Default")
      (node (ref "D5") (pin "1") (pinfunction "1_1") (pintype "passive"))
      (node (ref "Q4") (pin "3") (pinfunction "C_3") (pintype "passive"))
      (node (ref "R16") (pin "2") (pinfunction "2_2") (pintype "passive"))
    )
    (net (code "95") (name "Net-(Q7-B)") (class "Default")
      (node (ref "C11") (pin "1") (pinfunction "1_1") (pintype "passive"))
      (node (ref "Q7") (pin "1") (pinfunction "B_1") (pintype "passive"))
      (node (ref "R19") (pin "1") (pinfunction "1_1") (pintype "passive"))
      (node (ref "R5") (pin "2") (pinfunction "2_2") (pintype "passive"))
    )
    (net (code "96") (name "Net-(Q9-B)") (class "Default")
      (node (ref "Q9") (pin "1") (pinfunction "B_1") (pintype "passive"))
      (node (ref "R3") (pin "2") (pinfunction "2_2") (pintype "passive"))
    )
    (net (code "97") (name "Net-(Q9-E)") (class "Default")
      (node (ref "Q9") (pin "2") (pinfunction "E_2") (pintype "passive"))
      (node (ref "R15") (pin "1") (pinfunction "1_1") (pintype "passive"))
    )
    (net (code "98") (name "Net-(Q10-B)") (class "Default")
      (node (ref "Q10") (pin "1") (pinfunction "B_1") (pintype "passive"))
      (node (ref "R12") (pin "2") (pinfunction "2_2") (pintype "passive"))
    )
    (net (code "99") (name "Net-(Q10-C)") (class "Default")
      (node (ref "C36") (pin "1") (pinfunction "1_1") (pintype "passive"))
      (node (ref "Q10") (pin "3") (pinfunction "C_3") (pintype "passive"))
      (node (ref "U1") (pin "7") (pinfunction "HOLD#_7") (pintype "passive"))
      (node (ref "U1") (pin "8") (pinfunction "VDD_8") (pintype "passive"))
    )
    (net (code "100") (name "Net-(Q11-B)") (class "Default")
      (node (ref "Q11") (pin "1") (pinfunction "B_1") (pintype "passive"))
      (node (ref "R38") (pin "2") (pinfunction "2_2") (pintype "passive"))
    )
    (net (code "101") (name "Net-(Q22-B)") (class "Default")
      (node (ref "Q22") (pin "1") (pinfunction "B_1") (pintype "passive"))
      (node (ref "R61") (pin "1") (pinfunction "1_1") (pintype "passive"))
    )
    (net (code "102") (name "Net-(Q22-E)") (class "Default")
      (node (ref "Q22") (pin "2") (pinfunction "E_2") (pintype "passive"))
      (node (ref "R58") (pin "2") (pinfunction "2_2") (pintype "passive"))
      (node (ref "R59") (pin "1") (pinfunction "1_1") (pintype "passive"))
    )
    (net (code "103") (name "Net-(U7-VDD15)") (class "Default")
      (node (ref "C38") (pin "1") (pinfunction "1_1") (pintype "passive"))
      (node (ref "U7") (pin "62") (pinfunction "VDD15_62") (pintype "passive"))
    )
    (net (code "104") (name "VCC") (class "Default")
      (node (ref "C13") (pin "2") (pinfunction "2_2") (pintype "passive"))
      (node (ref "C30") (pin "1") (pinfunction "1_1") (pintype "passive"))
      (node (ref "C31") (pin "1") (pinfunction "1_1") (pintype "passive"))
      (node (ref "C44") (pin "2") (pinfunction "2_2") (pintype "passive"))
      (node (ref "C48") (pin "2") (pinfunction "2_2") (pintype "passive"))
      (node (ref "D1") (pin "1") (pinfunction "1_1") (pintype "passive"))
      (node (ref "J8") (pin "5") (pinfunction "5_5") (pintype "passive"))
      (node (ref "P2") (pin "5") (pinfunction "5_5") (pintype "passive"))
      (node (ref "Q10") (pin "2") (pinfunction "E_2") (pintype "passive"))
      (node (ref "Q4") (pin "2") (pinfunction "E_2") (pintype "passive"))
      (node (ref "R27") (pin "2") (pinfunction "2_2") (pintype "passive"))
      (node (ref "R59") (pin "2") (pinfunction "2_2") (pintype "passive"))
      (node (ref "R93") (pin "1") (pintype "passive"))
      (node (ref "R94") (pin "2") (pintype "passive"))
      (node (ref "U7") (pin "64") (pinfunction "VDD(VDDA)_64") (pintype "passive"))
      (node (ref "U7") (pin "66") (pinfunction "VREFP_66") (pintype "passive"))
      (node (ref "U7") (pin "67") (pinfunction "VBAT_67") (pintype "passive"))
      (node (ref "U8") (pin "8") (pinfunction "VCC_8") (pintype "passive"))
      (node (ref "VCC") (pin "1") (pinfunction "1_1") (pintype "passive"))
    )
    (net (code "105") (name "VIN") (class "Default")
      (node (ref "Q1") (pin "2") (pinfunction "E_2") (pintype "passive"))
      (node (ref "R10") (pin "2") (pintype "passive"))
    )
    (net (code "106") (name "unconnected-(U7-PB13{slash}SEG11{slash}UART1_RX{slash}LPUART1_RX-Pad34)") (class "Default")
      (node (ref "U7") (pin "34") (pinfunction "PB13/SEG11/UART1_RX/LPUART1_RX_34") (pintype "passive"))
    )
    (net (code "107") (name "unconnected-(U7-PE7{slash}COMP3_OUT-Pad69)") (class "Default")
      (node (ref "U7") (pin "69") (pinfunction "PE7/COMP3_OUT_69") (pintype "passive"))
    )
  )
)
